# ThunderBolt_Nova.net
KiCad netlist of a schematic drawn in EAGLE
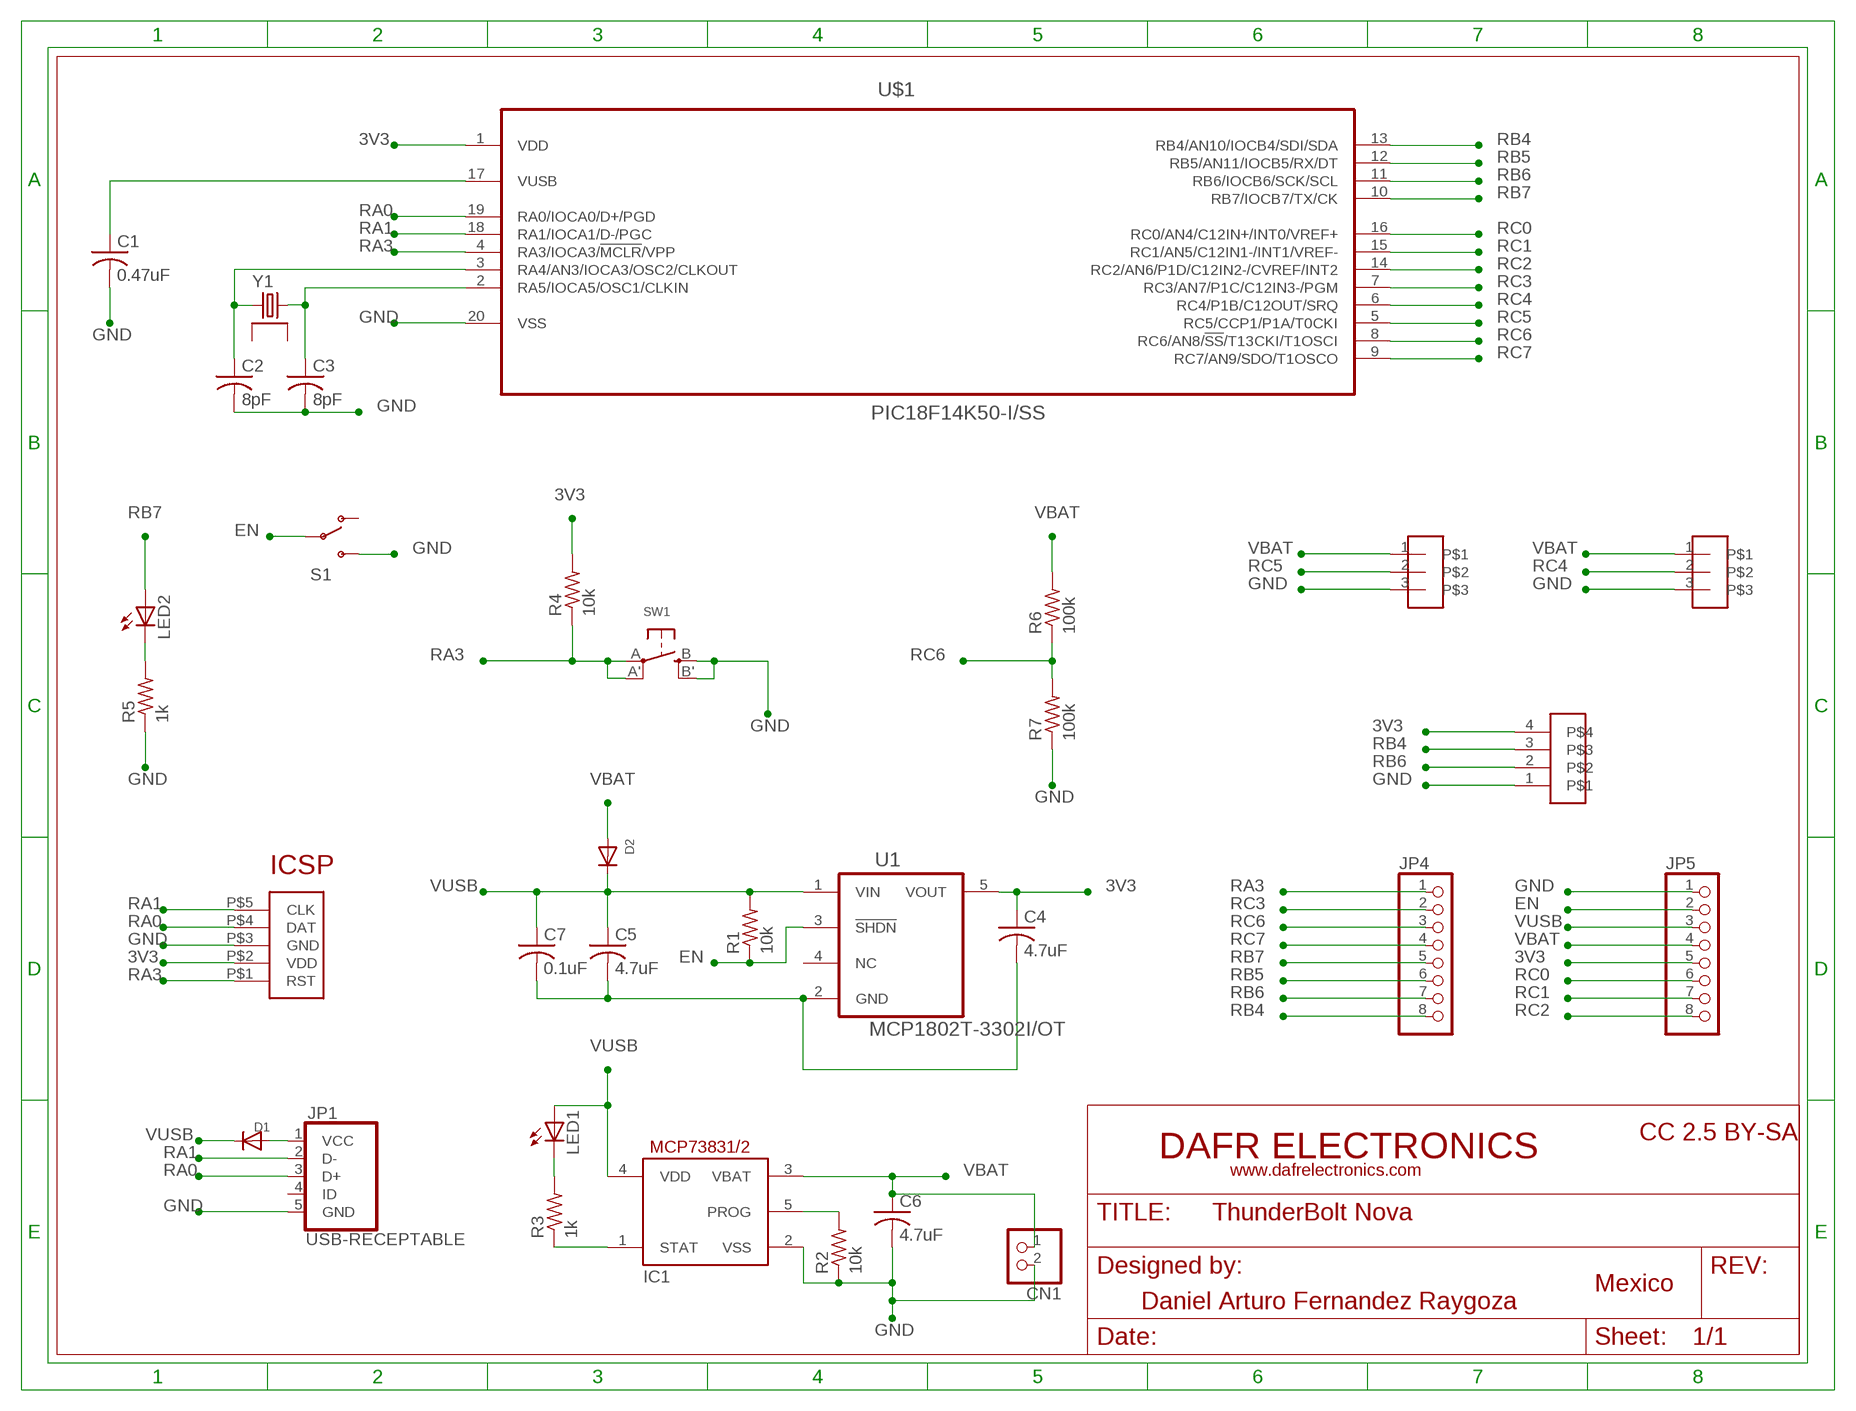
[diagram p0: schematic, sheet 1]

(export (version "E")
  (design (tool "Eeschema 10.0.6"))
  (components
    (comp (ref "C1")
      (value "0.47uF")
      (footprint "eagle-import:C0805K")
      (libsource (lib "eagle-import") (part "C-USC0805K"))
    )
    (comp (ref "C2")
      (value "8pF")
      (footprint "eagle-import:C0805K")
      (libsource (lib "eagle-import") (part "C-USC0805K"))
    )
    (comp (ref "C3")
      (value "8pF")
      (footprint "eagle-import:C0805K")
      (libsource (lib "eagle-import") (part "C-USC0805K"))
    )
    (comp (ref "C4")
      (value "4.7uF")
      (footprint "eagle-import:C0805K")
      (libsource (lib "eagle-import") (part "C-USC0805K"))
    )
    (comp (ref "C5")
      (value "4.7uF")
      (footprint "eagle-import:C0805K")
      (libsource (lib "eagle-import") (part "C-USC0805K"))
    )
    (comp (ref "C6")
      (value "4.7uF")
      (footprint "eagle-import:C0805K")
      (libsource (lib "eagle-import") (part "C-USC0805K"))
    )
    (comp (ref "C7")
      (value "0.1uF")
      (footprint "eagle-import:C0603K")
      (libsource (lib "eagle-import") (part "C-USC0603K"))
    )
    (comp (ref "CN1")
      (value "JST_2PIN-SMT-RA")
      (footprint "eagle-import:JST-PH-2-SMT-RA")
      (libsource (lib "eagle-import") (part "JST_2PIN-SMT-RA"))
    )
    (comp (ref "D1")
      (value "DIODESOD-123")
      (footprint "eagle-import:SOD-123")
      (libsource (lib "eagle-import") (part "DIODESOD-123"))
    )
    (comp (ref "D2")
      (value "DIODESOD-123")
      (footprint "eagle-import:SOD-123")
      (libsource (lib "eagle-import") (part "DIODESOD-123"))
    )
    (comp (ref "IC1")
      (value "MCP73831/OT")
      (footprint "eagle-import:SOT23-5L")
      (libsource (lib "eagle-import") (part "MCP73831/OT"))
    )
    (comp (ref "JP1")
      (value "USB-RECEPTABLE")
      (footprint "eagle-import:FCI-10103594-0001LF")
      (libsource (lib "eagle-import") (part "USB-RECEPTABLE"))
    )
    (comp (ref "JP4")
      (value "PINHD-1X8BIG")
      (footprint "eagle-import:1X08-BIG")
      (libsource (lib "eagle-import") (part "PINHD-1X8BIG"))
    )
    (comp (ref "JP5")
      (value "PINHD-1X8BIG")
      (footprint "eagle-import:1X08-BIG")
      (libsource (lib "eagle-import") (part "PINHD-1X8BIG"))
    )
    (comp (ref "LED1")
      (value "LEDCHIPLED_1206")
      (footprint "eagle-import:CHIPLED_1206")
      (libsource (lib "eagle-import") (part "LEDCHIPLED_1206"))
    )
    (comp (ref "LED2")
      (value "LEDCHIPLED_1206")
      (footprint "eagle-import:CHIPLED_1206")
      (libsource (lib "eagle-import") (part "LEDCHIPLED_1206"))
    )
    (comp (ref "R1")
      (value "10k")
      (footprint "eagle-import:R0805")
      (libsource (lib "eagle-import") (part "R-US_R0805"))
    )
    (comp (ref "R2")
      (value "10k")
      (footprint "eagle-import:R0805")
      (libsource (lib "eagle-import") (part "R-US_R0805"))
    )
    (comp (ref "R3")
      (value "1k")
      (footprint "eagle-import:R0805")
      (libsource (lib "eagle-import") (part "R-US_R0805"))
    )
    (comp (ref "R4")
      (value "10k")
      (footprint "eagle-import:R0805")
      (libsource (lib "eagle-import") (part "R-US_R0805"))
    )
    (comp (ref "R5")
      (value "1k")
      (footprint "eagle-import:R0805")
      (libsource (lib "eagle-import") (part "R-US_R0805"))
    )
    (comp (ref "R6")
      (value "100k")
      (footprint "eagle-import:R0805")
      (libsource (lib "eagle-import") (part "R-US_R0805"))
    )
    (comp (ref "R7")
      (value "100k")
      (footprint "eagle-import:R0805")
      (libsource (lib "eagle-import") (part "R-US_R0805"))
    )
    (comp (ref "S1")
      (value "SWITCH-SPDT-SMD-A")
      (footprint "eagle-import:SWITCH-SPST-SMD-A")
      (libsource (lib "eagle-import") (part "SWITCH-SPDT-SMD-A"))
    )
    (comp (ref "SW1")
      (value "SWITCH_TACT_SMT4.6X2.8")
      (footprint "eagle-import:BTN_KMR2_4.6X2.8")
      (libsource (lib "eagle-import") (part "SWITCH_TACT_SMT4.6X2.8"))
    )
    (comp (ref "U$1")
      (value "PIC18F14K50-I/SS")
      (footprint "eagle-import:SOP65P780X200-20N")
      (libsource (lib "eagle-import") (part "PIC18F14K50-I/SS"))
    )
    (comp (ref "U$2")
      (value "ICSP_POGO")
      (footprint "eagle-import:ICSP_POGO")
      (libsource (lib "eagle-import") (part "ICSP_POGO"))
    )
    (comp (ref "U$5")
      (value "PIN1X3")
      (footprint "eagle-import:PIN1X3")
      (libsource (lib "eagle-import") (part "PIN1X3"))
    )
    (comp (ref "U$6")
      (value "PIN1X3")
      (footprint "eagle-import:PIN1X3")
      (libsource (lib "eagle-import") (part "PIN1X3"))
    )
    (comp (ref "U$7")
      (value "PIN1X4")
      (footprint "eagle-import:PIN1X4")
      (libsource (lib "eagle-import") (part "PIN1X4"))
    )
    (comp (ref "U1")
      (value "MCP1802T-3302I/OT")
      (footprint "eagle-import:SOT95P270X145-5N")
      (libsource (lib "eagle-import") (part "MCP1802T-3302I/OT"))
    )
    (comp (ref "Y1")
      (value "GRX-330")
      (footprint "eagle-import:OSC3225")
      (libsource (lib "eagle-import") (part "GRX-330"))
    )
  )
  (nets
    (net (code "1") (name "/3V3") (class "Default")
      (node (ref "C4") (pin "1") (pinfunction "1_1") (pintype "passive"))
      (node (ref "JP5") (pin "5") (pinfunction "5_5") (pintype "passive"))
      (node (ref "R4") (pin "2") (pinfunction "2_2") (pintype "passive"))
      (node (ref "U$1") (pin "1") (pinfunction "VDD_1") (pintype "power_in"))
      (node (ref "U$2") (pin "P$2") (pinfunction "VDD_P$2") (pintype "bidirectional"))
      (node (ref "U$7") (pin "4") (pinfunction "P$4_4") (pintype "bidirectional"))
      (node (ref "U1") (pin "5") (pinfunction "VOUT_5") (pintype "output"))
    )
    (net (code "2") (name "/EN") (class "Default")
      (node (ref "JP5") (pin "2") (pinfunction "2_2") (pintype "passive"))
      (node (ref "R1") (pin "1") (pinfunction "1_1") (pintype "passive"))
      (node (ref "S1") (pin "2") (pinfunction "P_2") (pintype "passive"))
      (node (ref "U1") (pin "3") (pinfunction "~{SHDN}_3") (pintype "input"))
    )
    (net (code "3") (name "/GND") (class "Default")
      (node (ref "C1") (pin "2") (pinfunction "2_2") (pintype "passive"))
      (node (ref "C2") (pin "2") (pinfunction "2_2") (pintype "passive"))
      (node (ref "C3") (pin "2") (pinfunction "2_2") (pintype "passive"))
      (node (ref "C6") (pin "2") (pinfunction "2_2") (pintype "passive"))
      (node (ref "CN1") (pin "2") (pinfunction "1_2") (pintype "passive"))
      (node (ref "IC1") (pin "2") (pinfunction "VSS_2") (pintype "power_in"))
      (node (ref "JP1") (pin "5") (pinfunction "GND_5") (pintype "bidirectional"))
      (node (ref "JP5") (pin "1") (pinfunction "1_1") (pintype "passive"))
      (node (ref "R2") (pin "1") (pinfunction "1_1") (pintype "passive"))
      (node (ref "R5") (pin "1") (pinfunction "1_1") (pintype "passive"))
      (node (ref "R7") (pin "1") (pinfunction "1_1") (pintype "passive"))
      (node (ref "S1") (pin "3") (pinfunction "S_3") (pintype "passive"))
      (node (ref "SW1") (pin "B") (pinfunction "S_B") (pintype "passive"))
      (node (ref "SW1") (pin "B'") (pinfunction "S1_B'") (pintype "passive"))
      (node (ref "U$1") (pin "20") (pinfunction "VSS_20") (pintype "passive"))
      (node (ref "U$2") (pin "P$3") (pinfunction "GND_P$3") (pintype "bidirectional"))
      (node (ref "U$5") (pin "3") (pinfunction "P$3_3") (pintype "bidirectional"))
      (node (ref "U$6") (pin "3") (pinfunction "P$3_3") (pintype "bidirectional"))
      (node (ref "U$7") (pin "1") (pinfunction "P$1_1") (pintype "bidirectional"))
    )
    (net (code "4") (name "/RA0") (class "Default")
      (node (ref "JP1") (pin "3") (pinfunction "D+_3") (pintype "bidirectional"))
      (node (ref "U$1") (pin "19") (pinfunction "RA0/IOCA0/D+/PGD_19") (pintype "bidirectional"))
      (node (ref "U$2") (pin "P$4") (pinfunction "DAT_P$4") (pintype "bidirectional"))
    )
    (net (code "5") (name "/RA1") (class "Default")
      (node (ref "JP1") (pin "2") (pinfunction "D-_2") (pintype "bidirectional"))
      (node (ref "U$1") (pin "18") (pinfunction "RA1/IOCA1/D-/PGC_18") (pintype "bidirectional"))
      (node (ref "U$2") (pin "P$5") (pinfunction "CLK_P$5") (pintype "bidirectional"))
    )
    (net (code "6") (name "/RA3") (class "Default")
      (node (ref "JP4") (pin "1") (pinfunction "1_1") (pintype "passive"))
      (node (ref "R4") (pin "1") (pinfunction "1_1") (pintype "passive"))
      (node (ref "SW1") (pin "A") (pinfunction "P_A") (pintype "passive"))
      (node (ref "SW1") (pin "A'") (pinfunction "P1_A'") (pintype "passive"))
      (node (ref "U$1") (pin "4") (pinfunction "RA3/IOCA3/~{MCLR}/VPP_4") (pintype "bidirectional"))
      (node (ref "U$2") (pin "P$1") (pinfunction "RST_P$1") (pintype "bidirectional"))
    )
    (net (code "7") (name "/RB4") (class "Default")
      (node (ref "JP4") (pin "8") (pinfunction "8_8") (pintype "passive"))
      (node (ref "U$1") (pin "13") (pinfunction "RB4/AN10/IOCB4/SDI/SDA_13") (pintype "bidirectional"))
      (node (ref "U$7") (pin "3") (pinfunction "P$3_3") (pintype "bidirectional"))
    )
    (net (code "8") (name "/RB5") (class "Default")
      (node (ref "JP4") (pin "6") (pinfunction "6_6") (pintype "passive"))
      (node (ref "U$1") (pin "12") (pinfunction "RB5/AN11/IOCB5/RX/DT_12") (pintype "bidirectional"))
    )
    (net (code "9") (name "/RB6") (class "Default")
      (node (ref "JP4") (pin "7") (pinfunction "7_7") (pintype "passive"))
      (node (ref "U$1") (pin "11") (pinfunction "RB6/IOCB6/SCK/SCL_11") (pintype "bidirectional"))
      (node (ref "U$7") (pin "2") (pinfunction "P$2_2") (pintype "bidirectional"))
    )
    (net (code "10") (name "/RB7") (class "Default")
      (node (ref "JP4") (pin "5") (pinfunction "5_5") (pintype "passive"))
      (node (ref "LED2") (pin "A") (pinfunction "A_A") (pintype "passive"))
      (node (ref "U$1") (pin "10") (pinfunction "RB7/IOCB7/TX/CK_10") (pintype "bidirectional"))
    )
    (net (code "11") (name "/RC0") (class "Default")
      (node (ref "JP5") (pin "6") (pinfunction "6_6") (pintype "passive"))
      (node (ref "U$1") (pin "16") (pinfunction "RC0/AN4/C12IN+/INT0/VREF+_16") (pintype "power_in"))
    )
    (net (code "12") (name "/RC1") (class "Default")
      (node (ref "JP5") (pin "7") (pinfunction "7_7") (pintype "passive"))
      (node (ref "U$1") (pin "15") (pinfunction "RC1/AN5/C12IN1-/INT1/VREF-_15") (pintype "power_in"))
    )
    (net (code "13") (name "/RC2") (class "Default")
      (node (ref "JP5") (pin "8") (pinfunction "8_8") (pintype "passive"))
      (node (ref "U$1") (pin "14") (pinfunction "RC2/AN6/P1D/C12IN2-/CVREF/INT2_14") (pintype "bidirectional"))
    )
    (net (code "14") (name "/RC3") (class "Default")
      (node (ref "JP4") (pin "2") (pinfunction "2_2") (pintype "passive"))
      (node (ref "U$1") (pin "7") (pinfunction "RC3/AN7/P1C/C12IN3-/PGM_7") (pintype "bidirectional"))
    )
    (net (code "15") (name "/RC4") (class "Default")
      (node (ref "U$1") (pin "6") (pinfunction "RC4/P1B/C12OUT/SRQ_6") (pintype "bidirectional"))
      (node (ref "U$5") (pin "2") (pinfunction "P$2_2") (pintype "bidirectional"))
    )
    (net (code "16") (name "/RC5") (class "Default")
      (node (ref "U$1") (pin "5") (pinfunction "RC5/CCP1/P1A/T0CKI_5") (pintype "bidirectional"))
      (node (ref "U$6") (pin "2") (pinfunction "P$2_2") (pintype "bidirectional"))
    )
    (net (code "17") (name "/RC6") (class "Default")
      (node (ref "JP4") (pin "3") (pinfunction "3_3") (pintype "passive"))
      (node (ref "R6") (pin "1") (pinfunction "1_1") (pintype "passive"))
      (node (ref "R7") (pin "2") (pinfunction "2_2") (pintype "passive"))
      (node (ref "U$1") (pin "8") (pinfunction "RC6/AN8/~{SS}/T13CKI/T1OSCI_8") (pintype "bidirectional"))
    )
    (net (code "18") (name "/RC7") (class "Default")
      (node (ref "JP4") (pin "4") (pinfunction "4_4") (pintype "passive"))
      (node (ref "U$1") (pin "9") (pinfunction "RC7/AN9/SDO/T1OSCO_9") (pintype "bidirectional"))
    )
    (net (code "19") (name "/VBAT") (class "Default")
      (node (ref "C6") (pin "1") (pinfunction "1_1") (pintype "passive"))
      (node (ref "CN1") (pin "1") (pinfunction "2_1") (pintype "passive"))
      (node (ref "D2") (pin "A") (pinfunction "A_A") (pintype "passive"))
      (node (ref "IC1") (pin "3") (pinfunction "VBAT_3") (pintype "bidirectional"))
      (node (ref "JP5") (pin "4") (pinfunction "4_4") (pintype "passive"))
      (node (ref "R6") (pin "2") (pinfunction "2_2") (pintype "passive"))
      (node (ref "U$5") (pin "1") (pinfunction "P$1_1") (pintype "bidirectional"))
      (node (ref "U$6") (pin "1") (pinfunction "P$1_1") (pintype "bidirectional"))
    )
    (net (code "20") (name "/VUSB") (class "Default")
      (node (ref "C5") (pin "1") (pinfunction "1_1") (pintype "passive"))
      (node (ref "C7") (pin "1") (pinfunction "1_1") (pintype "passive"))
      (node (ref "D1") (pin "C") (pinfunction "C_C") (pintype "passive"))
      (node (ref "D2") (pin "C") (pinfunction "C_C") (pintype "passive"))
      (node (ref "IC1") (pin "4") (pinfunction "VDD_4") (pintype "power_in"))
      (node (ref "JP5") (pin "3") (pinfunction "3_3") (pintype "passive"))
      (node (ref "LED1") (pin "A") (pinfunction "A_A") (pintype "passive"))
      (node (ref "R1") (pin "2") (pinfunction "2_2") (pintype "passive"))
      (node (ref "U1") (pin "1") (pinfunction "VIN_1") (pintype "power_in"))
    )
    (net (code "21") (name "Net-(IC1-PROG)") (class "Default")
      (node (ref "IC1") (pin "5") (pinfunction "PROG_5") (pintype "input"))
      (node (ref "R2") (pin "2") (pinfunction "2_2") (pintype "passive"))
    )
    (net (code "22") (name "Net-(IC1-STAT)") (class "Default")
      (node (ref "IC1") (pin "1") (pinfunction "STAT_1") (pintype "output"))
      (node (ref "R3") (pin "1") (pinfunction "1_1") (pintype "passive"))
    )
    (net (code "23") (name "Net-(JP1-VCC)") (class "Default")
      (node (ref "D1") (pin "A") (pinfunction "A_A") (pintype "passive"))
      (node (ref "JP1") (pin "1") (pinfunction "VCC_1") (pintype "bidirectional"))
    )
    (net (code "24") (name "Net-(LED1-PadC)") (class "Default")
      (node (ref "LED1") (pin "C") (pinfunction "C_C") (pintype "passive"))
      (node (ref "R3") (pin "2") (pinfunction "2_2") (pintype "passive"))
    )
    (net (code "25") (name "Net-(LED2-PadC)") (class "Default")
      (node (ref "LED2") (pin "C") (pinfunction "C_C") (pintype "passive"))
      (node (ref "R5") (pin "2") (pinfunction "2_2") (pintype "passive"))
    )
    (net (code "26") (name "Net-(U$1-RA4{slash}AN3{slash}IOCA3{slash}OSC2{slash}CLKOUT)") (class "Default")
      (node (ref "C2") (pin "1") (pinfunction "1_1") (pintype "passive"))
      (node (ref "U$1") (pin "3") (pinfunction "RA4/AN3/IOCA3/OSC2/CLKOUT_3") (pintype "input"))
      (node (ref "Y1") (pin "P$1") (pinfunction "1_P$1") (pintype "passive"))
    )
    (net (code "27") (name "Net-(U$1-RA5{slash}IOCA5{slash}OSC1{slash}CLKIN)") (class "Default")
      (node (ref "C3") (pin "1") (pinfunction "1_1") (pintype "passive"))
      (node (ref "U$1") (pin "2") (pinfunction "RA5/IOCA5/OSC1/CLKIN_2") (pintype "bidirectional"))
      (node (ref "Y1") (pin "P$3") (pinfunction "3_P$3") (pintype "passive"))
    )
    (net (code "28") (name "Net-(U$1-VUSB)") (class "Default")
      (node (ref "C1") (pin "1") (pinfunction "1_1") (pintype "passive"))
      (node (ref "U$1") (pin "17") (pinfunction "VUSB_17") (pintype "input"))
    )
    (net (code "29") (name "Net-(U1-GND)") (class "Default")
      (node (ref "C4") (pin "2") (pinfunction "2_2") (pintype "passive"))
      (node (ref "C5") (pin "2") (pinfunction "2_2") (pintype "passive"))
      (node (ref "C7") (pin "2") (pinfunction "2_2") (pintype "passive"))
      (node (ref "U1") (pin "2") (pinfunction "GND_2") (pintype "passive"))
    )
    (net (code "30") (name "unconnected-(JP1-ID-Pad4)") (class "Default")
      (node (ref "JP1") (pin "4") (pinfunction "ID_4") (pintype "bidirectional"))
    )
    (net (code "31") (name "unconnected-(S1-O-Pad1)") (class "Default")
      (node (ref "S1") (pin "1") (pinfunction "O_1") (pintype "passive"))
    )
    (net (code "32") (name "unconnected-(U1-NC-Pad4)") (class "Default")
      (node (ref "U1") (pin "4") (pinfunction "NC_4") (pintype "no_connect"))
    )
    (net (code "33") (name "unconnected-(Y1-2-PadP$2)") (class "Default")
      (node (ref "Y1") (pin "P$2") (pinfunction "2_P$2") (pintype "passive"))
    )
    (net (code "34") (name "unconnected-(Y1-4-PadP$4)") (class "Default")
      (node (ref "Y1") (pin "P$4") (pinfunction "4_P$4") (pintype "passive"))
    )
  )
)
